# PI_SCH.net
KiCad netlist of a schematic drawn in EasyEDA
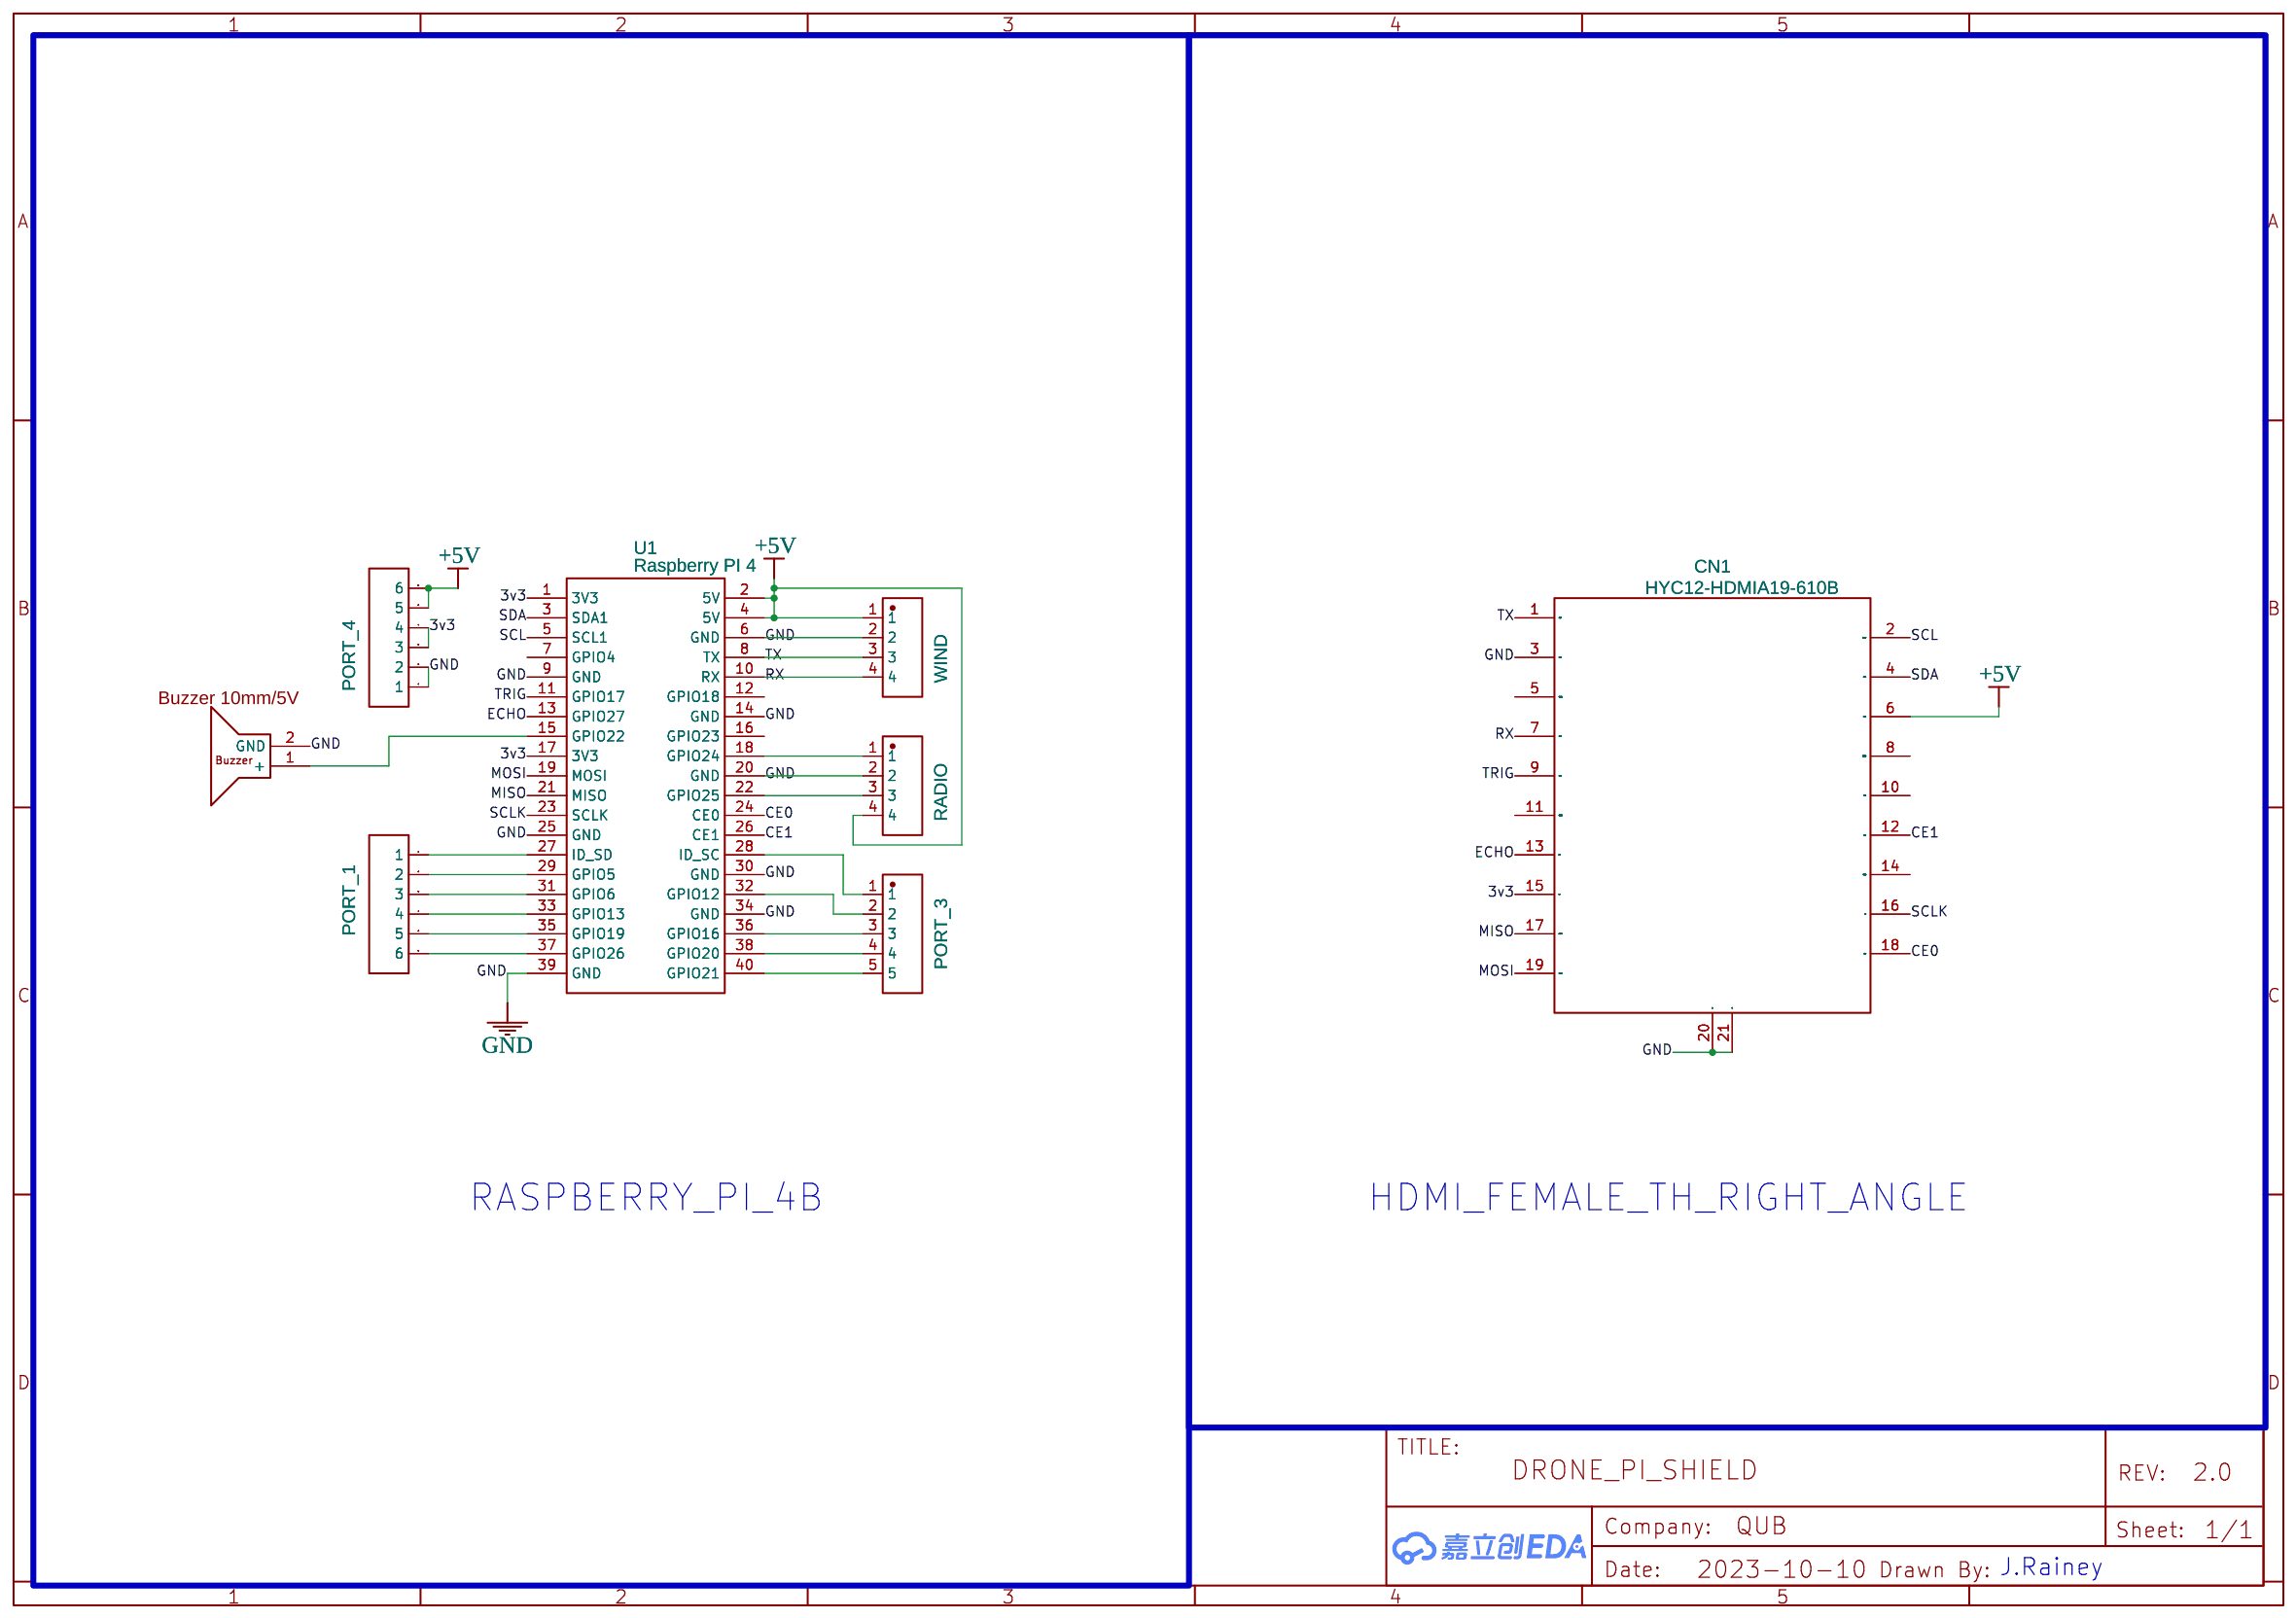
[diagram p0: schematic sheet]

(export (version "E")
  (design (tool "Eeschema 10.0.6"))
  (components
    (comp (ref "BUZZER1")
      (value "Buzzer 10mm/5V")
      (fields (field (name "BOM_Manufacturer Part") "BUZZER"))
      (libsource (lib "") (part "Buzzer 10mm/5V"))
    )
    (comp (ref "CN1")
      (value "HYC12-HDMIA19-610B")
      (fields (field (name "BOM_Supplier Part") "C711354"))
      (libsource (lib "") (part "HYC12-HDMIA19-610B"))
    )
    (comp (ref "PORT_1")
      (value "HEADER-MALE-2.54_1X6")
      (fields
        (field (name "BOM_Manufacturer Part") "Header-Male-2.54_1x6")
        (field (name "BOM_Supplier Part") "C37208")
      )
      (libsource (lib "") (part "HEADER-MALE-2.54_1X6_1"))
    )
    (comp (ref "PORT_3")
      (value "PZ254V-11-05P")
      (fields (field (name "BOM_Supplier Part") "C492404"))
      (libsource (lib "") (part "PZ254V-11-05P"))
    )
    (comp (ref "PORT_4")
      (value "HEADER-MALE-2.54_1X6")
      (fields
        (field (name "BOM_Manufacturer Part") "Header-Male-2.54_1x6")
        (field (name "BOM_Supplier Part") "C37208")
      )
      (libsource (lib "") (part "HEADER-MALE-2.54_1X6"))
    )
    (comp (ref "RADIO")
      (value "PZ254V-11-04P")
      (fields (field (name "BOM_Supplier Part") "C492403"))
      (libsource (lib "") (part "PZ254V-11-04P_1"))
    )
    (comp (ref "U1") (value "Raspberry PI 4") (libsource (lib "") (part "Raspberry PI 4")))
    (comp (ref "WIND")
      (value "PZ254V-11-04P")
      (fields (field (name "BOM_Supplier Part") "C492403"))
      (libsource (lib "") (part "PZ254V-11-04P"))
    )
  )
  (nets
    (net (code "1") (name "+5V") (class "Default")
      (node (ref "CN1") (pin "6") (pinfunction "TMDS_Data_1-_6") (pintype "unspecified"))
      (node (ref "PORT_4") (pin "5") (pinfunction "5_5") (pintype "input"))
      (node (ref "PORT_4") (pin "6") (pinfunction "6_6") (pintype "input"))
      (node (ref "RADIO") (pin "4") (pinfunction "4_4") (pintype "unspecified"))
      (node (ref "U1") (pin "2") (pinfunction "5V_2") (pintype "unspecified"))
      (node (ref "U1") (pin "4") (pinfunction "5V_4") (pintype "unspecified"))
      (node (ref "WIND") (pin "1") (pinfunction "1_1") (pintype "unspecified"))
    )
    (net (code "2") (name "/3v3") (class "Default")
      (node (ref "CN1") (pin "15") (pinfunction "SCL_15") (pintype "unspecified"))
      (node (ref "PORT_4") (pin "3") (pinfunction "3_3") (pintype "input"))
      (node (ref "PORT_4") (pin "4") (pinfunction "4_4") (pintype "input"))
      (node (ref "U1") (pin "1") (pinfunction "3V3_1") (pintype "unspecified"))
      (node (ref "U1") (pin "17") (pinfunction "3V3_17") (pintype "unspecified"))
    )
    (net (code "3") (name "/CE0") (class "Default")
      (node (ref "CN1") (pin "18") (pinfunction "+5V_Power_18") (pintype "unspecified"))
      (node (ref "U1") (pin "24") (pinfunction "CE0_24") (pintype "unspecified"))
    )
    (net (code "4") (name "/CE1") (class "Default")
      (node (ref "CN1") (pin "12") (pinfunction "TMDS_Clock-_12") (pintype "unspecified"))
      (node (ref "U1") (pin "26") (pinfunction "CE1_26") (pintype "unspecified"))
    )
    (net (code "5") (name "/ECHO") (class "Default")
      (node (ref "CN1") (pin "13") (pinfunction "CEC_13") (pintype "unspecified"))
      (node (ref "U1") (pin "13") (pinfunction "GPIO27_13") (pintype "unspecified"))
    )
    (net (code "6") (name "/MISO") (class "Default")
      (node (ref "CN1") (pin "17") (pinfunction "DDC/CEC_Ground_17") (pintype "unspecified"))
      (node (ref "U1") (pin "21") (pinfunction "MISO_21") (pintype "unspecified"))
    )
    (net (code "7") (name "/MOSI") (class "Default")
      (node (ref "CN1") (pin "19") (pinfunction "Hot_Plug_Detect_19") (pintype "unspecified"))
      (node (ref "U1") (pin "19") (pinfunction "MOSI_19") (pintype "unspecified"))
    )
    (net (code "8") (name "/RX") (class "Default")
      (node (ref "CN1") (pin "7") (pinfunction "TMDS_Data_0+_7") (pintype "unspecified"))
      (node (ref "U1") (pin "10") (pinfunction "RX_10") (pintype "unspecified"))
      (node (ref "WIND") (pin "4") (pinfunction "4_4") (pintype "unspecified"))
    )
    (net (code "9") (name "/SCL") (class "Default")
      (node (ref "CN1") (pin "2") (pinfunction "TMDS_Data_2_Shield_2") (pintype "unspecified"))
      (node (ref "U1") (pin "5") (pinfunction "SCL1_5") (pintype "unspecified"))
    )
    (net (code "10") (name "/SCLK") (class "Default")
      (node (ref "CN1") (pin "16") (pinfunction "SDA_16") (pintype "unspecified"))
      (node (ref "U1") (pin "23") (pinfunction "SCLK_23") (pintype "unspecified"))
    )
    (net (code "11") (name "/SDA") (class "Default")
      (node (ref "CN1") (pin "4") (pinfunction "TMDS_Data_1+_4") (pintype "unspecified"))
      (node (ref "U1") (pin "3") (pinfunction "SDA1_3") (pintype "unspecified"))
    )
    (net (code "12") (name "/TRIG") (class "Default")
      (node (ref "CN1") (pin "9") (pinfunction "TMDS_Data_0-_9") (pintype "unspecified"))
      (node (ref "U1") (pin "11") (pinfunction "GPIO17_11") (pintype "unspecified"))
    )
    (net (code "13") (name "/TX") (class "Default")
      (node (ref "CN1") (pin "1") (pinfunction "TMDS_Data_2+_1") (pintype "unspecified"))
      (node (ref "U1") (pin "8") (pinfunction "TX_8") (pintype "unspecified"))
      (node (ref "WIND") (pin "3") (pinfunction "3_3") (pintype "unspecified"))
    )
    (net (code "14") (name "GND") (class "Default")
      (node (ref "BUZZER1") (pin "2") (pinfunction "GND_2") (pintype "unspecified"))
      (node (ref "CN1") (pin "20") (pinfunction "EH_20") (pintype "unspecified"))
      (node (ref "CN1") (pin "21") (pinfunction "EH_21") (pintype "unspecified"))
      (node (ref "CN1") (pin "3") (pinfunction "TMDS_Data_2-_3") (pintype "unspecified"))
      (node (ref "PORT_4") (pin "1") (pinfunction "1_1") (pintype "input"))
      (node (ref "PORT_4") (pin "2") (pinfunction "2_2") (pintype "input"))
      (node (ref "RADIO") (pin "2") (pinfunction "2_2") (pintype "unspecified"))
      (node (ref "U1") (pin "14") (pinfunction "GND_14") (pintype "unspecified"))
      (node (ref "U1") (pin "20") (pinfunction "GND_20") (pintype "unspecified"))
      (node (ref "U1") (pin "25") (pinfunction "GND_25") (pintype "unspecified"))
      (node (ref "U1") (pin "30") (pinfunction "GND_30") (pintype "unspecified"))
      (node (ref "U1") (pin "34") (pinfunction "GND_34") (pintype "unspecified"))
      (node (ref "U1") (pin "39") (pinfunction "GND_39") (pintype "unspecified"))
      (node (ref "U1") (pin "6") (pinfunction "GND_6") (pintype "unspecified"))
      (node (ref "U1") (pin "9") (pinfunction "GND_9") (pintype "unspecified"))
      (node (ref "WIND") (pin "2") (pinfunction "2_2") (pintype "unspecified"))
    )
    (net (code "15") (name "Net-(BUZZER1-+)") (class "Default")
      (node (ref "BUZZER1") (pin "1") (pinfunction "+_1") (pintype "unspecified"))
      (node (ref "U1") (pin "15") (pinfunction "GPIO22_15") (pintype "unspecified"))
    )
    (net (code "16") (name "Net-(U1-GPIO5)") (class "Default")
      (node (ref "PORT_1") (pin "2") (pinfunction "2_2") (pintype "input"))
      (node (ref "U1") (pin "29") (pinfunction "GPIO5_29") (pintype "unspecified"))
    )
    (net (code "17") (name "Net-(U1-GPIO6)") (class "Default")
      (node (ref "PORT_1") (pin "3") (pinfunction "3_3") (pintype "input"))
      (node (ref "U1") (pin "31") (pinfunction "GPIO6_31") (pintype "unspecified"))
    )
    (net (code "18") (name "Net-(U1-GPIO12)") (class "Default")
      (node (ref "PORT_3") (pin "2") (pinfunction "2_2") (pintype "unspecified"))
      (node (ref "U1") (pin "32") (pinfunction "GPIO12_32") (pintype "unspecified"))
    )
    (net (code "19") (name "Net-(U1-GPIO13)") (class "Default")
      (node (ref "PORT_1") (pin "4") (pinfunction "4_4") (pintype "input"))
      (node (ref "U1") (pin "33") (pinfunction "GPIO13_33") (pintype "unspecified"))
    )
    (net (code "20") (name "Net-(U1-GPIO16)") (class "Default")
      (node (ref "PORT_3") (pin "3") (pinfunction "3_3") (pintype "unspecified"))
      (node (ref "U1") (pin "36") (pinfunction "GPIO16_36") (pintype "unspecified"))
    )
    (net (code "21") (name "Net-(U1-GPIO19)") (class "Default")
      (node (ref "PORT_1") (pin "5") (pinfunction "5_5") (pintype "input"))
      (node (ref "U1") (pin "35") (pinfunction "GPIO19_35") (pintype "unspecified"))
    )
    (net (code "22") (name "Net-(U1-GPIO20)") (class "Default")
      (node (ref "PORT_3") (pin "4") (pinfunction "4_4") (pintype "unspecified"))
      (node (ref "U1") (pin "38") (pinfunction "GPIO20_38") (pintype "unspecified"))
    )
    (net (code "23") (name "Net-(U1-GPIO21)") (class "Default")
      (node (ref "PORT_3") (pin "5") (pinfunction "5_5") (pintype "unspecified"))
      (node (ref "U1") (pin "40") (pinfunction "GPIO21_40") (pintype "unspecified"))
    )
    (net (code "24") (name "Net-(U1-GPIO24)") (class "Default")
      (node (ref "RADIO") (pin "1") (pinfunction "1_1") (pintype "unspecified"))
      (node (ref "U1") (pin "18") (pinfunction "GPIO24_18") (pintype "unspecified"))
    )
    (net (code "25") (name "Net-(U1-GPIO25)") (class "Default")
      (node (ref "RADIO") (pin "3") (pinfunction "3_3") (pintype "unspecified"))
      (node (ref "U1") (pin "22") (pinfunction "GPIO25_22") (pintype "unspecified"))
    )
    (net (code "26") (name "Net-(U1-GPIO26)") (class "Default")
      (node (ref "PORT_1") (pin "6") (pinfunction "6_6") (pintype "input"))
      (node (ref "U1") (pin "37") (pinfunction "GPIO26_37") (pintype "unspecified"))
    )
    (net (code "27") (name "Net-(U1-ID_SC)") (class "Default")
      (node (ref "PORT_3") (pin "1") (pinfunction "1_1") (pintype "unspecified"))
      (node (ref "U1") (pin "28") (pinfunction "ID_SC_28") (pintype "unspecified"))
    )
    (net (code "28") (name "Net-(U1-ID_SD)") (class "Default")
      (node (ref "PORT_1") (pin "1") (pinfunction "1_1") (pintype "input"))
      (node (ref "U1") (pin "27") (pinfunction "ID_SD_27") (pintype "unspecified"))
    )
    (net (code "29") (name "unconnected-(CN1-Reserved_(N.C.)-Pad14)") (class "Default")
      (node (ref "CN1") (pin "14") (pinfunction "Reserved_(N.C.)_14") (pintype "unspecified"))
    )
    (net (code "30") (name "unconnected-(CN1-TMDS_Clock+-Pad10)") (class "Default")
      (node (ref "CN1") (pin "10") (pinfunction "TMDS_Clock+_10") (pintype "unspecified"))
    )
    (net (code "31") (name "unconnected-(CN1-TMDS_Clock_Shield-Pad11)") (class "Default")
      (node (ref "CN1") (pin "11") (pinfunction "TMDS_Clock_Shield_11") (pintype "unspecified"))
    )
    (net (code "32") (name "unconnected-(CN1-TMDS_Data_0_Shield-Pad8)") (class "Default")
      (node (ref "CN1") (pin "8") (pinfunction "TMDS_Data_0_Shield_8") (pintype "unspecified"))
    )
    (net (code "33") (name "unconnected-(CN1-TMDS_Data_1_Shield-Pad5)") (class "Default")
      (node (ref "CN1") (pin "5") (pinfunction "TMDS_Data_1_Shield_5") (pintype "unspecified"))
    )
    (net (code "34") (name "unconnected-(U1-GPIO4-Pad7)") (class "Default")
      (node (ref "U1") (pin "7") (pinfunction "GPIO4_7") (pintype "unspecified"))
    )
    (net (code "35") (name "unconnected-(U1-GPIO18-Pad12)") (class "Default")
      (node (ref "U1") (pin "12") (pinfunction "GPIO18_12") (pintype "unspecified"))
    )
    (net (code "36") (name "unconnected-(U1-GPIO23-Pad16)") (class "Default")
      (node (ref "U1") (pin "16") (pinfunction "GPIO23_16") (pintype "unspecified"))
    )
  )
)
